# DC27-top.net
KiCad netlist of a schematic drawn in EAGLE
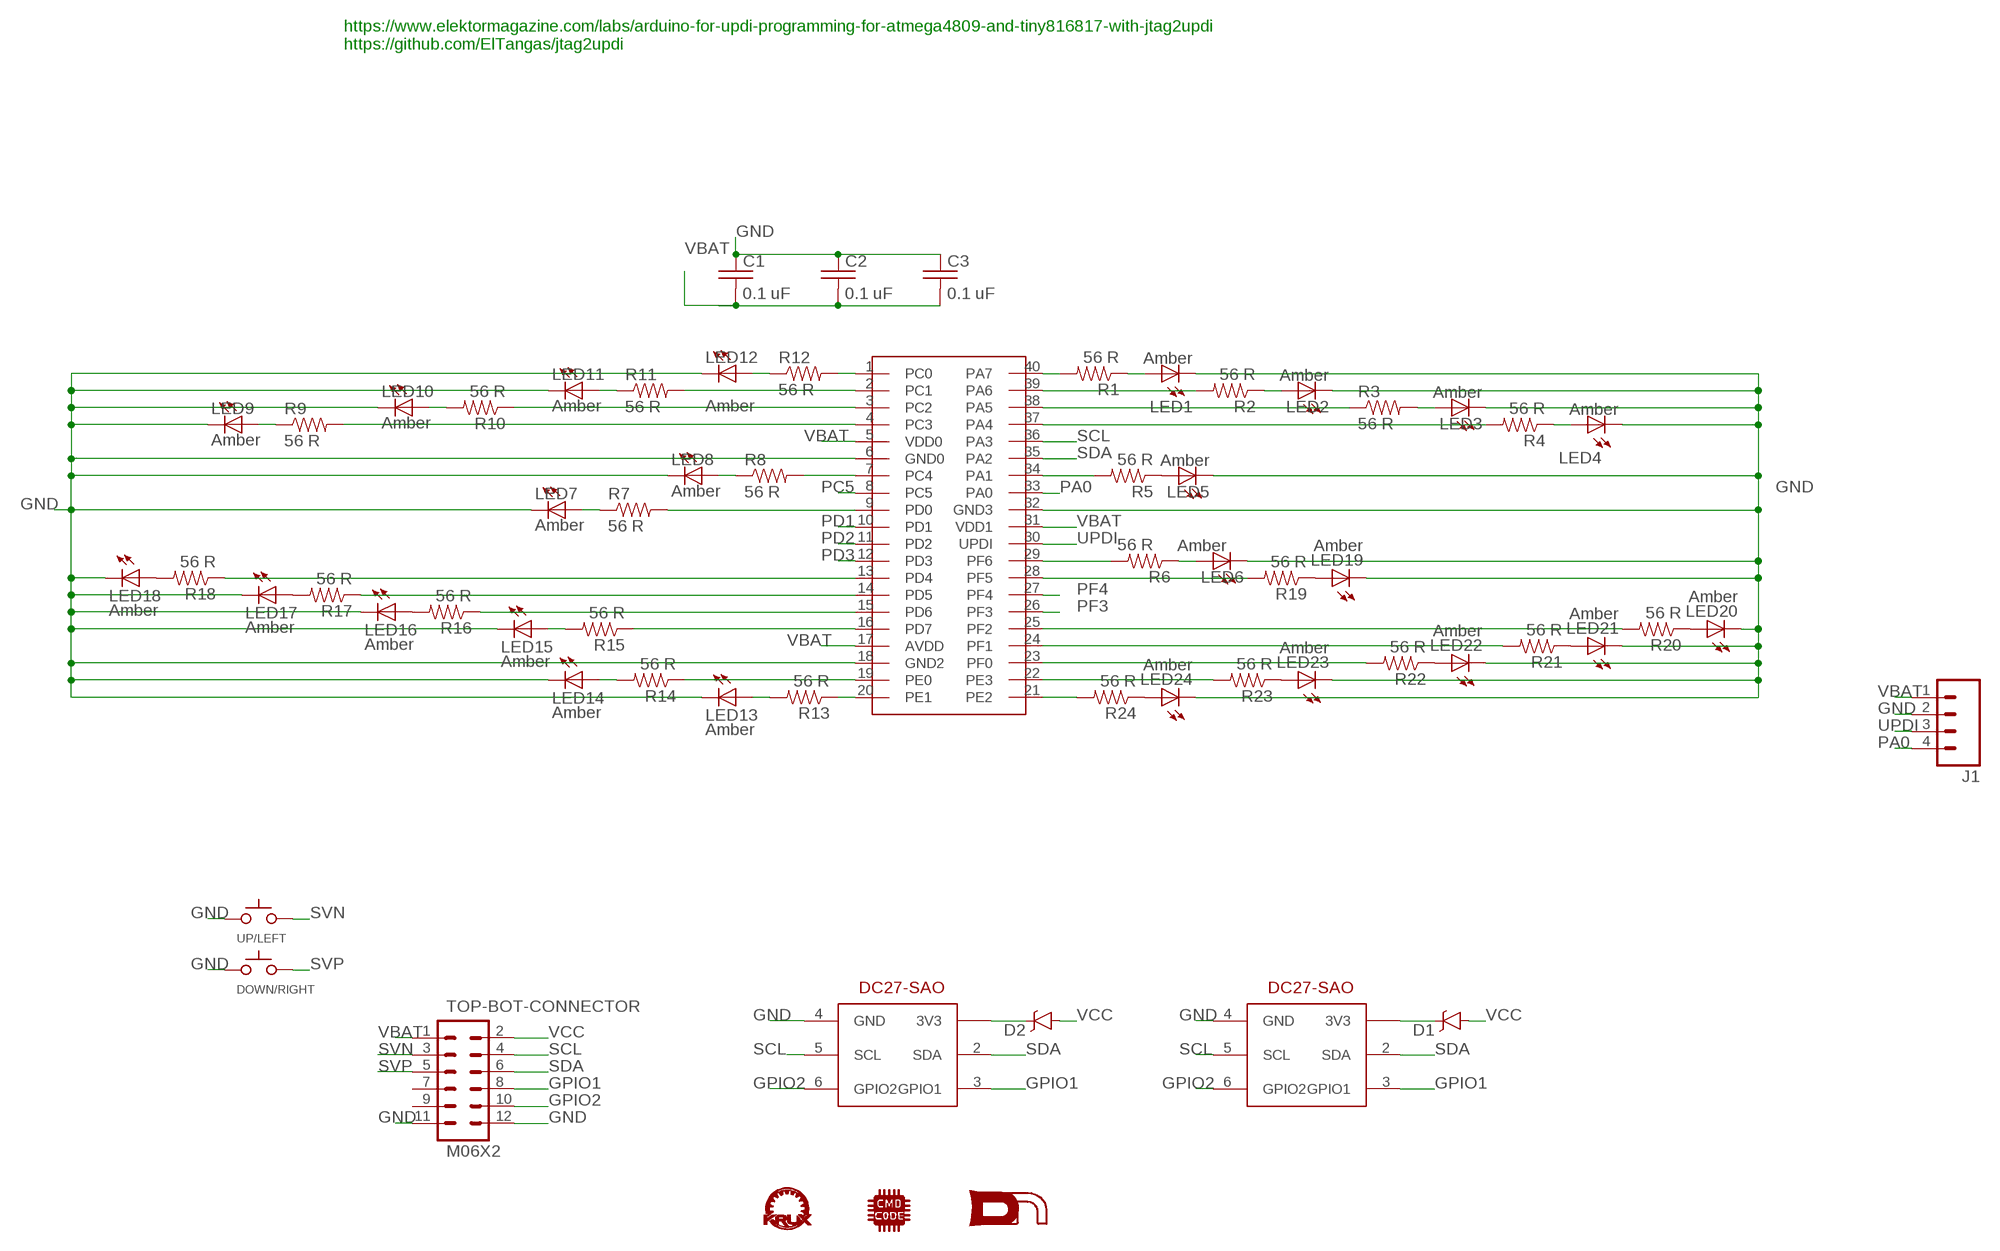
[diagram p0: schematic, sheet 1]

(export (version "E")
  (design (tool "Eeschema 10.0.6"))
  (components
    (comp (ref "C1")
      (value "0.1 uF")
      (footprint "eagle-import:C1206")
      (libsource (lib "eagle-import") (part "C-USC1206"))
    )
    (comp (ref "C2")
      (value "0.1 uF")
      (footprint "eagle-import:C1206")
      (libsource (lib "eagle-import") (part "C-USC1206"))
    )
    (comp (ref "C3")
      (value "0.1 uF")
      (footprint "eagle-import:C1206")
      (libsource (lib "eagle-import") (part "C-USC1206"))
    )
    (comp (ref "D1")
      (value "DIODE-SCHOTTKYDIOAD-TH")
      (footprint "eagle-import:DIOAD1060W80L520D270")
      (libsource (lib "eagle-import") (part "DIODE-SCHOTTKYDIOAD-TH"))
    )
    (comp (ref "D2")
      (value "DIODE-SCHOTTKYDIOAD-TH")
      (footprint "eagle-import:DIOAD1060W80L520D270")
      (libsource (lib "eagle-import") (part "DIODE-SCHOTTKYDIOAD-TH"))
    )
    (comp (ref "DOWN/RIGHT")
      (value "SWITCH_TACTILETACTILE-2PIN-NARROW")
      (footprint "eagle-import:TACTILE-2PIN-NARROW")
      (libsource (lib "eagle-import") (part "SWITCH_TACTILETACTILE-2PIN-NARROW"))
    )
    (comp (ref "J1")
      (value "M04PTH")
      (footprint "eagle-import:1X04")
      (libsource (lib "eagle-import") (part "M04PTH"))
    )
    (comp (ref "LED1")
      (value "Amber")
      (footprint "eagle-import:GULLWING_LED")
      (libsource (lib "eagle-import") (part "LEDREVERSEMOUNT"))
    )
    (comp (ref "LED2")
      (value "Amber")
      (footprint "eagle-import:GULLWING_LED")
      (libsource (lib "eagle-import") (part "LEDREVERSEMOUNT"))
    )
    (comp (ref "LED3")
      (value "Amber")
      (footprint "eagle-import:GULLWING_LED")
      (libsource (lib "eagle-import") (part "LEDREVERSEMOUNT"))
    )
    (comp (ref "LED4")
      (value "Amber")
      (footprint "eagle-import:GULLWING_LED")
      (libsource (lib "eagle-import") (part "LEDREVERSEMOUNT"))
    )
    (comp (ref "LED5")
      (value "Amber")
      (footprint "eagle-import:GULLWING_LED")
      (libsource (lib "eagle-import") (part "LEDREVERSEMOUNT"))
    )
    (comp (ref "LED6")
      (value "Amber")
      (footprint "eagle-import:GULLWING_LED")
      (libsource (lib "eagle-import") (part "LEDREVERSEMOUNT"))
    )
    (comp (ref "LED7")
      (value "Amber")
      (footprint "eagle-import:GULLWING_LED")
      (libsource (lib "eagle-import") (part "LEDREVERSEMOUNT"))
    )
    (comp (ref "LED8")
      (value "Amber")
      (footprint "eagle-import:GULLWING_LED")
      (libsource (lib "eagle-import") (part "LEDREVERSEMOUNT"))
    )
    (comp (ref "LED9")
      (value "Amber")
      (footprint "eagle-import:GULLWING_LED")
      (libsource (lib "eagle-import") (part "LEDREVERSEMOUNT"))
    )
    (comp (ref "LED10")
      (value "Amber")
      (footprint "eagle-import:GULLWING_LED")
      (libsource (lib "eagle-import") (part "LEDREVERSEMOUNT"))
    )
    (comp (ref "LED11")
      (value "Amber")
      (footprint "eagle-import:GULLWING_LED")
      (libsource (lib "eagle-import") (part "LEDREVERSEMOUNT"))
    )
    (comp (ref "LED12")
      (value "Amber")
      (footprint "eagle-import:GULLWING_LED")
      (libsource (lib "eagle-import") (part "LEDREVERSEMOUNT"))
    )
    (comp (ref "LED13")
      (value "Amber")
      (footprint "eagle-import:GULLWING_LED")
      (libsource (lib "eagle-import") (part "LEDREVERSEMOUNT"))
    )
    (comp (ref "LED14")
      (value "Amber")
      (footprint "eagle-import:GULLWING_LED")
      (libsource (lib "eagle-import") (part "LEDREVERSEMOUNT"))
    )
    (comp (ref "LED15")
      (value "Amber")
      (footprint "eagle-import:GULLWING_LED")
      (libsource (lib "eagle-import") (part "LEDREVERSEMOUNT"))
    )
    (comp (ref "LED16")
      (value "Amber")
      (footprint "eagle-import:GULLWING_LED")
      (libsource (lib "eagle-import") (part "LEDREVERSEMOUNT"))
    )
    (comp (ref "LED17")
      (value "Amber")
      (footprint "eagle-import:GULLWING_LED")
      (libsource (lib "eagle-import") (part "LEDREVERSEMOUNT"))
    )
    (comp (ref "LED18")
      (value "Amber")
      (footprint "eagle-import:GULLWING_LED")
      (libsource (lib "eagle-import") (part "LEDREVERSEMOUNT"))
    )
    (comp (ref "LED19")
      (value "Amber")
      (footprint "eagle-import:GULLWING_LED")
      (libsource (lib "eagle-import") (part "LEDREVERSEMOUNT"))
    )
    (comp (ref "LED20")
      (value "Amber")
      (footprint "eagle-import:GULLWING_LED")
      (libsource (lib "eagle-import") (part "LEDREVERSEMOUNT"))
    )
    (comp (ref "LED21")
      (value "Amber")
      (footprint "eagle-import:GULLWING_LED")
      (libsource (lib "eagle-import") (part "LEDREVERSEMOUNT"))
    )
    (comp (ref "LED22")
      (value "Amber")
      (footprint "eagle-import:GULLWING_LED")
      (libsource (lib "eagle-import") (part "LEDREVERSEMOUNT"))
    )
    (comp (ref "LED23")
      (value "Amber")
      (footprint "eagle-import:GULLWING_LED")
      (libsource (lib "eagle-import") (part "LEDREVERSEMOUNT"))
    )
    (comp (ref "LED24")
      (value "Amber")
      (footprint "eagle-import:GULLWING_LED")
      (libsource (lib "eagle-import") (part "LEDREVERSEMOUNT"))
    )
    (comp (ref "R1")
      (value "56 R")
      (footprint "eagle-import:1206")
      (libsource (lib "eagle-import") (part "RESISTOR1206"))
    )
    (comp (ref "R2")
      (value "56 R")
      (footprint "eagle-import:1206")
      (libsource (lib "eagle-import") (part "RESISTOR1206"))
    )
    (comp (ref "R3")
      (value "56 R")
      (footprint "eagle-import:1206")
      (libsource (lib "eagle-import") (part "RESISTOR1206"))
    )
    (comp (ref "R4")
      (value "56 R")
      (footprint "eagle-import:1206")
      (libsource (lib "eagle-import") (part "RESISTOR1206"))
    )
    (comp (ref "R5")
      (value "56 R")
      (footprint "eagle-import:1206")
      (libsource (lib "eagle-import") (part "RESISTOR1206"))
    )
    (comp (ref "R6")
      (value "56 R")
      (footprint "eagle-import:1206")
      (libsource (lib "eagle-import") (part "RESISTOR1206"))
    )
    (comp (ref "R7")
      (value "56 R")
      (footprint "eagle-import:1206")
      (libsource (lib "eagle-import") (part "RESISTOR1206"))
    )
    (comp (ref "R8")
      (value "56 R")
      (footprint "eagle-import:1206")
      (libsource (lib "eagle-import") (part "RESISTOR1206"))
    )
    (comp (ref "R9")
      (value "56 R")
      (footprint "eagle-import:1206")
      (libsource (lib "eagle-import") (part "RESISTOR1206"))
    )
    (comp (ref "R10")
      (value "56 R")
      (footprint "eagle-import:1206")
      (libsource (lib "eagle-import") (part "RESISTOR1206"))
    )
    (comp (ref "R11")
      (value "56 R")
      (footprint "eagle-import:1206")
      (libsource (lib "eagle-import") (part "RESISTOR1206"))
    )
    (comp (ref "R12")
      (value "56 R")
      (footprint "eagle-import:1206")
      (libsource (lib "eagle-import") (part "RESISTOR1206"))
    )
    (comp (ref "R13")
      (value "56 R")
      (footprint "eagle-import:1206")
      (libsource (lib "eagle-import") (part "RESISTOR1206"))
    )
    (comp (ref "R14")
      (value "56 R")
      (footprint "eagle-import:1206")
      (libsource (lib "eagle-import") (part "RESISTOR1206"))
    )
    (comp (ref "R15")
      (value "56 R")
      (footprint "eagle-import:1206")
      (libsource (lib "eagle-import") (part "RESISTOR1206"))
    )
    (comp (ref "R16")
      (value "56 R")
      (footprint "eagle-import:1206")
      (libsource (lib "eagle-import") (part "RESISTOR1206"))
    )
    (comp (ref "R17")
      (value "56 R")
      (footprint "eagle-import:1206")
      (libsource (lib "eagle-import") (part "RESISTOR1206"))
    )
    (comp (ref "R18")
      (value "56 R")
      (footprint "eagle-import:1206")
      (libsource (lib "eagle-import") (part "RESISTOR1206"))
    )
    (comp (ref "R19")
      (value "56 R")
      (footprint "eagle-import:1206")
      (libsource (lib "eagle-import") (part "RESISTOR1206"))
    )
    (comp (ref "R20")
      (value "56 R")
      (footprint "eagle-import:1206")
      (libsource (lib "eagle-import") (part "RESISTOR1206"))
    )
    (comp (ref "R21")
      (value "56 R")
      (footprint "eagle-import:1206")
      (libsource (lib "eagle-import") (part "RESISTOR1206"))
    )
    (comp (ref "R22")
      (value "56 R")
      (footprint "eagle-import:1206")
      (libsource (lib "eagle-import") (part "RESISTOR1206"))
    )
    (comp (ref "R23")
      (value "56 R")
      (footprint "eagle-import:1206")
      (libsource (lib "eagle-import") (part "RESISTOR1206"))
    )
    (comp (ref "R24")
      (value "56 R")
      (footprint "eagle-import:1206")
      (libsource (lib "eagle-import") (part "RESISTOR1206"))
    )
    (comp (ref "TOP-BOT-CONNECTOR")
      (value "M06X2")
      (footprint "eagle-import:2X6")
      (libsource (lib "eagle-import") (part "M06X2"))
    )
    (comp (ref "U$1")
      (value "KRUX_LOGO")
      (footprint "eagle-import:KRUX_LOGO")
      (libsource (lib "eagle-import") (part "KRUX_LOGO"))
    )
    (comp (ref "U$2")
      (value "CMD_C0DE_LOGO")
      (footprint "eagle-import:CMD_C0DE_LOGO")
      (libsource (lib "eagle-import") (part "CMD_C0DE_LOGO"))
    )
    (comp (ref "U$3")
      (value "DC-27-SAO")
      (footprint "eagle-import:3X2")
      (libsource (lib "eagle-import") (part "DC-27-SAO"))
    )
    (comp (ref "U$4")
      (value "DC-27-SAO")
      (footprint "eagle-import:3X2")
      (libsource (lib "eagle-import") (part "DC-27-SAO"))
    )
    (comp (ref "U$5")
      (value "DN_LOGODC26")
      (footprint "eagle-import:DN_LOGO_DC26")
      (libsource (lib "eagle-import") (part "DN_LOGODC26"))
    )
    (comp (ref "U$6")
      (value "ATMEGA4809-PFATMEL4809-PF")
      (footprint "eagle-import:DIP1587W58P254L5175H635Q40B")
      (libsource (lib "eagle-import") (part "ATMEGA4809-PFATMEL4809-PF"))
    )
    (comp (ref "UP/LEFT")
      (value "SWITCH_TACTILETACTILE-2PIN-NARROW")
      (footprint "eagle-import:TACTILE-2PIN-NARROW")
      (libsource (lib "eagle-import") (part "SWITCH_TACTILETACTILE-2PIN-NARROW"))
    )
  )
  (nets
    (net (code "1") (name "/GND") (class "Default")
      (node (ref "C1") (pin "1") (pinfunction "1_1") (pintype "passive"))
      (node (ref "C2") (pin "1") (pinfunction "1_1") (pintype "passive"))
      (node (ref "C3") (pin "1") (pinfunction "1_1") (pintype "passive"))
      (node (ref "DOWN/RIGHT") (pin "P$2") (pinfunction "C_P$2") (pintype "passive"))
      (node (ref "J1") (pin "2") (pinfunction "2_2") (pintype "passive"))
      (node (ref "LED1") (pin "C") (pinfunction "C_C") (pintype "output"))
      (node (ref "LED10") (pin "C") (pinfunction "C_C") (pintype "output"))
      (node (ref "LED11") (pin "C") (pinfunction "C_C") (pintype "output"))
      (node (ref "LED12") (pin "C") (pinfunction "C_C") (pintype "output"))
      (node (ref "LED13") (pin "C") (pinfunction "C_C") (pintype "output"))
      (node (ref "LED14") (pin "C") (pinfunction "C_C") (pintype "output"))
      (node (ref "LED15") (pin "C") (pinfunction "C_C") (pintype "output"))
      (node (ref "LED16") (pin "C") (pinfunction "C_C") (pintype "output"))
      (node (ref "LED17") (pin "C") (pinfunction "C_C") (pintype "output"))
      (node (ref "LED18") (pin "C") (pinfunction "C_C") (pintype "output"))
      (node (ref "LED19") (pin "C") (pinfunction "C_C") (pintype "output"))
      (node (ref "LED2") (pin "C") (pinfunction "C_C") (pintype "output"))
      (node (ref "LED20") (pin "C") (pinfunction "C_C") (pintype "output"))
      (node (ref "LED21") (pin "C") (pinfunction "C_C") (pintype "output"))
      (node (ref "LED22") (pin "C") (pinfunction "C_C") (pintype "output"))
      (node (ref "LED23") (pin "C") (pinfunction "C_C") (pintype "output"))
      (node (ref "LED24") (pin "C") (pinfunction "C_C") (pintype "output"))
      (node (ref "LED3") (pin "C") (pinfunction "C_C") (pintype "output"))
      (node (ref "LED4") (pin "C") (pinfunction "C_C") (pintype "output"))
      (node (ref "LED5") (pin "C") (pinfunction "C_C") (pintype "output"))
      (node (ref "LED6") (pin "C") (pinfunction "C_C") (pintype "output"))
      (node (ref "LED7") (pin "C") (pinfunction "C_C") (pintype "output"))
      (node (ref "LED8") (pin "C") (pinfunction "C_C") (pintype "output"))
      (node (ref "LED9") (pin "C") (pinfunction "C_C") (pintype "output"))
      (node (ref "TOP-BOT-CONNECTOR") (pin "11") (pinfunction "11_11") (pintype "passive"))
      (node (ref "TOP-BOT-CONNECTOR") (pin "12") (pinfunction "12_12") (pintype "passive"))
      (node (ref "U$3") (pin "4") (pinfunction "GND_4") (pintype "power_in"))
      (node (ref "U$4") (pin "4") (pinfunction "GND_4") (pintype "power_in"))
      (node (ref "U$6") (pin "18") (pinfunction "GND2_18") (pintype "bidirectional"))
      (node (ref "U$6") (pin "32") (pinfunction "GND3_32") (pintype "bidirectional"))
      (node (ref "U$6") (pin "6") (pinfunction "GND0_6") (pintype "bidirectional"))
      (node (ref "UP/LEFT") (pin "P$2") (pinfunction "C_P$2") (pintype "passive"))
    )
    (net (code "2") (name "/GPIO1") (class "Default")
      (node (ref "TOP-BOT-CONNECTOR") (pin "8") (pinfunction "8_8") (pintype "passive"))
      (node (ref "U$3") (pin "3") (pinfunction "GPIO1_3") (pintype "bidirectional"))
      (node (ref "U$4") (pin "3") (pinfunction "GPIO1_3") (pintype "bidirectional"))
    )
    (net (code "3") (name "/GPIO2") (class "Default")
      (node (ref "TOP-BOT-CONNECTOR") (pin "10") (pinfunction "10_10") (pintype "passive"))
      (node (ref "U$3") (pin "6") (pinfunction "GPIO2_6") (pintype "bidirectional"))
      (node (ref "U$4") (pin "6") (pinfunction "GPIO2_6") (pintype "bidirectional"))
    )
    (net (code "4") (name "/PA0") (class "Default")
      (node (ref "J1") (pin "4") (pinfunction "4_4") (pintype "passive"))
      (node (ref "U$6") (pin "33") (pinfunction "PA0_33") (pintype "bidirectional"))
    )
    (net (code "5") (name "/PC5") (class "Default")
      (node (ref "U$6") (pin "8") (pinfunction "PC5_8") (pintype "bidirectional"))
    )
    (net (code "6") (name "/PD1") (class "Default")
      (node (ref "U$6") (pin "10") (pinfunction "PD1_10") (pintype "bidirectional"))
    )
    (net (code "7") (name "/PD2") (class "Default")
      (node (ref "U$6") (pin "11") (pinfunction "PD2_11") (pintype "bidirectional"))
    )
    (net (code "8") (name "/PD3") (class "Default")
      (node (ref "U$6") (pin "12") (pinfunction "PD3_12") (pintype "bidirectional"))
    )
    (net (code "9") (name "/PF3") (class "Default")
      (node (ref "U$6") (pin "26") (pinfunction "PF3_26") (pintype "bidirectional"))
    )
    (net (code "10") (name "/PF4") (class "Default")
      (node (ref "U$6") (pin "27") (pinfunction "PF4_27") (pintype "bidirectional"))
    )
    (net (code "11") (name "/SCL") (class "Default")
      (node (ref "TOP-BOT-CONNECTOR") (pin "4") (pinfunction "4_4") (pintype "passive"))
      (node (ref "U$3") (pin "5") (pinfunction "SCL_5") (pintype "bidirectional"))
      (node (ref "U$4") (pin "5") (pinfunction "SCL_5") (pintype "bidirectional"))
      (node (ref "U$6") (pin "36") (pinfunction "PA3_36") (pintype "bidirectional"))
    )
    (net (code "12") (name "/SDA") (class "Default")
      (node (ref "TOP-BOT-CONNECTOR") (pin "6") (pinfunction "6_6") (pintype "passive"))
      (node (ref "U$3") (pin "2") (pinfunction "SDA_2") (pintype "bidirectional"))
      (node (ref "U$4") (pin "2") (pinfunction "SDA_2") (pintype "bidirectional"))
      (node (ref "U$6") (pin "35") (pinfunction "PA2_35") (pintype "bidirectional"))
    )
    (net (code "13") (name "/SVN") (class "Default")
      (node (ref "TOP-BOT-CONNECTOR") (pin "3") (pinfunction "3_3") (pintype "passive"))
      (node (ref "UP/LEFT") (pin "P$1") (pinfunction "A_P$1") (pintype "passive"))
    )
    (net (code "14") (name "/SVP") (class "Default")
      (node (ref "DOWN/RIGHT") (pin "P$1") (pinfunction "A_P$1") (pintype "passive"))
      (node (ref "TOP-BOT-CONNECTOR") (pin "5") (pinfunction "5_5") (pintype "passive"))
    )
    (net (code "15") (name "/UPDI") (class "Default")
      (node (ref "J1") (pin "3") (pinfunction "3_3") (pintype "passive"))
      (node (ref "U$6") (pin "30") (pinfunction "UPDI_30") (pintype "bidirectional"))
    )
    (net (code "16") (name "/VBAT") (class "Default")
      (node (ref "C1") (pin "2") (pinfunction "2_2") (pintype "passive"))
      (node (ref "C2") (pin "2") (pinfunction "2_2") (pintype "passive"))
      (node (ref "C3") (pin "2") (pinfunction "2_2") (pintype "passive"))
      (node (ref "J1") (pin "1") (pinfunction "1_1") (pintype "passive"))
      (node (ref "TOP-BOT-CONNECTOR") (pin "1") (pinfunction "1_1") (pintype "passive"))
      (node (ref "U$6") (pin "17") (pinfunction "AVDD_17") (pintype "power_in"))
      (node (ref "U$6") (pin "31") (pinfunction "VDD1_31") (pintype "power_in"))
      (node (ref "U$6") (pin "5") (pinfunction "VDD0_5") (pintype "power_in"))
    )
    (net (code "17") (name "/VCC") (class "Default")
      (node (ref "D1") (pin "A") (pinfunction "A_A") (pintype "passive"))
      (node (ref "D2") (pin "A") (pinfunction "A_A") (pintype "passive"))
      (node (ref "TOP-BOT-CONNECTOR") (pin "2") (pinfunction "2_2") (pintype "passive"))
    )
    (net (code "18") (name "Net-(LED1-PadA)") (class "Default")
      (node (ref "LED1") (pin "A") (pinfunction "A_A") (pintype "input"))
      (node (ref "R1") (pin "1") (pinfunction "1_1") (pintype "passive"))
    )
    (net (code "19") (name "Net-(LED2-PadA)") (class "Default")
      (node (ref "LED2") (pin "A") (pinfunction "A_A") (pintype "input"))
      (node (ref "R2") (pin "1") (pinfunction "1_1") (pintype "passive"))
    )
    (net (code "20") (name "Net-(LED3-PadA)") (class "Default")
      (node (ref "LED3") (pin "A") (pinfunction "A_A") (pintype "input"))
      (node (ref "R3") (pin "2") (pinfunction "2_2") (pintype "passive"))
    )
    (net (code "21") (name "Net-(LED4-PadA)") (class "Default")
      (node (ref "LED4") (pin "A") (pinfunction "A_A") (pintype "input"))
      (node (ref "R4") (pin "1") (pinfunction "1_1") (pintype "passive"))
    )
    (net (code "22") (name "Net-(LED5-PadA)") (class "Default")
      (node (ref "LED5") (pin "A") (pinfunction "A_A") (pintype "input"))
      (node (ref "R5") (pin "1") (pinfunction "1_1") (pintype "passive"))
    )
    (net (code "23") (name "Net-(LED6-PadA)") (class "Default")
      (node (ref "LED6") (pin "A") (pinfunction "A_A") (pintype "input"))
      (node (ref "R6") (pin "1") (pinfunction "1_1") (pintype "passive"))
    )
    (net (code "24") (name "Net-(LED7-PadA)") (class "Default")
      (node (ref "LED7") (pin "A") (pinfunction "A_A") (pintype "input"))
      (node (ref "R7") (pin "1") (pinfunction "1_1") (pintype "passive"))
    )
    (net (code "25") (name "Net-(LED8-PadA)") (class "Default")
      (node (ref "LED8") (pin "A") (pinfunction "A_A") (pintype "input"))
      (node (ref "R8") (pin "1") (pinfunction "1_1") (pintype "passive"))
    )
    (net (code "26") (name "Net-(LED9-PadA)") (class "Default")
      (node (ref "LED9") (pin "A") (pinfunction "A_A") (pintype "input"))
      (node (ref "R9") (pin "1") (pinfunction "1_1") (pintype "passive"))
    )
    (net (code "27") (name "Net-(LED10-PadA)") (class "Default")
      (node (ref "LED10") (pin "A") (pinfunction "A_A") (pintype "input"))
      (node (ref "R10") (pin "2") (pinfunction "2_2") (pintype "passive"))
    )
    (net (code "28") (name "Net-(LED11-PadA)") (class "Default")
      (node (ref "LED11") (pin "A") (pinfunction "A_A") (pintype "input"))
      (node (ref "R11") (pin "1") (pinfunction "1_1") (pintype "passive"))
    )
    (net (code "29") (name "Net-(LED12-PadA)") (class "Default")
      (node (ref "LED12") (pin "A") (pinfunction "A_A") (pintype "input"))
      (node (ref "R12") (pin "1") (pinfunction "1_1") (pintype "passive"))
    )
    (net (code "30") (name "Net-(LED13-PadA)") (class "Default")
      (node (ref "LED13") (pin "A") (pinfunction "A_A") (pintype "input"))
      (node (ref "R13") (pin "2") (pinfunction "2_2") (pintype "passive"))
    )
    (net (code "31") (name "Net-(LED14-PadA)") (class "Default")
      (node (ref "LED14") (pin "A") (pinfunction "A_A") (pintype "input"))
      (node (ref "R14") (pin "2") (pinfunction "2_2") (pintype "passive"))
    )
    (net (code "32") (name "Net-(LED15-PadA)") (class "Default")
      (node (ref "LED15") (pin "A") (pinfunction "A_A") (pintype "input"))
      (node (ref "R15") (pin "2") (pinfunction "2_2") (pintype "passive"))
    )
    (net (code "33") (name "Net-(LED16-PadA)") (class "Default")
      (node (ref "LED16") (pin "A") (pinfunction "A_A") (pintype "input"))
      (node (ref "R16") (pin "2") (pinfunction "2_2") (pintype "passive"))
    )
    (net (code "34") (name "Net-(LED17-PadA)") (class "Default")
      (node (ref "LED17") (pin "A") (pinfunction "A_A") (pintype "input"))
      (node (ref "R17") (pin "2") (pinfunction "2_2") (pintype "passive"))
    )
    (net (code "35") (name "Net-(LED18-PadA)") (class "Default")
      (node (ref "LED18") (pin "A") (pinfunction "A_A") (pintype "input"))
      (node (ref "R18") (pin "2") (pinfunction "2_2") (pintype "passive"))
    )
    (net (code "36") (name "Net-(LED19-PadA)") (class "Default")
      (node (ref "LED19") (pin "A") (pinfunction "A_A") (pintype "input"))
      (node (ref "R19") (pin "1") (pinfunction "1_1") (pintype "passive"))
    )
    (net (code "37") (name "Net-(LED20-PadA)") (class "Default")
      (node (ref "LED20") (pin "A") (pinfunction "A_A") (pintype "input"))
      (node (ref "R20") (pin "1") (pinfunction "1_1") (pintype "passive"))
    )
    (net (code "38") (name "Net-(LED21-PadA)") (class "Default")
      (node (ref "LED21") (pin "A") (pinfunction "A_A") (pintype "input"))
      (node (ref "R21") (pin "1") (pinfunction "1_1") (pintype "passive"))
    )
    (net (code "39") (name "Net-(LED22-PadA)") (class "Default")
      (node (ref "LED22") (pin "A") (pinfunction "A_A") (pintype "input"))
      (node (ref "R22") (pin "1") (pinfunction "1_1") (pintype "passive"))
    )
    (net (code "40") (name "Net-(LED23-PadA)") (class "Default")
      (node (ref "LED23") (pin "A") (pinfunction "A_A") (pintype "input"))
      (node (ref "R23") (pin "1") (pinfunction "1_1") (pintype "passive"))
    )
    (net (code "41") (name "Net-(LED24-PadA)") (class "Default")
      (node (ref "LED24") (pin "A") (pinfunction "A_A") (pintype "input"))
      (node (ref "R24") (pin "1") (pinfunction "1_1") (pintype "passive"))
    )
    (net (code "42") (name "Net-(U$3-3V3)") (class "Default")
      (node (ref "D2") (pin "C") (pinfunction "C_C") (pintype "passive"))
      (node (ref "U$3") (pin "1") (pinfunction "3V3_1") (pintype "power_in"))
    )
    (net (code "43") (name "Net-(U$4-3V3)") (class "Default")
      (node (ref "D1") (pin "C") (pinfunction "C_C") (pintype "passive"))
      (node (ref "U$4") (pin "1") (pinfunction "3V3_1") (pintype "power_in"))
    )
    (net (code "44") (name "Net-(U$6-PA1)") (class "Default")
      (node (ref "R5") (pin "2") (pinfunction "2_2") (pintype "passive"))
      (node (ref "U$6") (pin "34") (pinfunction "PA1_34") (pintype "bidirectional"))
    )
    (net (code "45") (name "Net-(U$6-PA4)") (class "Default")
      (node (ref "R4") (pin "2") (pinfunction "2_2") (pintype "passive"))
      (node (ref "U$6") (pin "37") (pinfunction "PA4_37") (pintype "bidirectional"))
    )
    (net (code "46") (name "Net-(U$6-PA5)") (class "Default")
      (node (ref "R3") (pin "1") (pinfunction "1_1") (pintype "passive"))
      (node (ref "U$6") (pin "38") (pinfunction "PA5_38") (pintype "bidirectional"))
    )
    (net (code "47") (name "Net-(U$6-PA6)") (class "Default")
      (node (ref "R2") (pin "2") (pinfunction "2_2") (pintype "passive"))
      (node (ref "U$6") (pin "39") (pinfunction "PA6_39") (pintype "bidirectional"))
    )
    (net (code "48") (name "Net-(U$6-PA7)") (class "Default")
      (node (ref "R1") (pin "2") (pinfunction "2_2") (pintype "passive"))
      (node (ref "U$6") (pin "40") (pinfunction "PA7_40") (pintype "bidirectional"))
    )
    (net (code "49") (name "Net-(U$6-PC0)") (class "Default")
      (node (ref "R12") (pin "2") (pinfunction "2_2") (pintype "passive"))
      (node (ref "U$6") (pin "1") (pinfunction "PC0_1") (pintype "bidirectional"))
    )
    (net (code "50") (name "Net-(U$6-PC1)") (class "Default")
      (node (ref "R11") (pin "2") (pinfunction "2_2") (pintype "passive"))
      (node (ref "U$6") (pin "2") (pinfunction "PC1_2") (pintype "bidirectional"))
    )
    (net (code "51") (name "Net-(U$6-PC2)") (class "Default")
      (node (ref "R10") (pin "1") (pinfunction "1_1") (pintype "passive"))
      (node (ref "U$6") (pin "3") (pinfunction "PC2_3") (pintype "bidirectional"))
    )
    (net (code "52") (name "Net-(U$6-PC3)") (class "Default")
      (node (ref "R9") (pin "2") (pinfunction "2_2") (pintype "passive"))
      (node (ref "U$6") (pin "4") (pinfunction "PC3_4") (pintype "bidirectional"))
    )
    (net (code "53") (name "Net-(U$6-PC4)") (class "Default")
      (node (ref "R8") (pin "2") (pinfunction "2_2") (pintype "passive"))
      (node (ref "U$6") (pin "7") (pinfunction "PC4_7") (pintype "bidirectional"))
    )
    (net (code "54") (name "Net-(U$6-PD0)") (class "Default")
      (node (ref "R7") (pin "2") (pinfunction "2_2") (pintype "passive"))
      (node (ref "U$6") (pin "9") (pinfunction "PD0_9") (pintype "bidirectional"))
    )
    (net (code "55") (name "Net-(U$6-PD4)") (class "Default")
      (node (ref "R18") (pin "1") (pinfunction "1_1") (pintype "passive"))
      (node (ref "U$6") (pin "13") (pinfunction "PD4_13") (pintype "bidirectional"))
    )
    (net (code "56") (name "Net-(U$6-PD5)") (class "Default")
      (node (ref "R17") (pin "1") (pinfunction "1_1") (pintype "passive"))
      (node (ref "U$6") (pin "14") (pinfunction "PD5_14") (pintype "bidirectional"))
    )
    (net (code "57") (name "Net-(U$6-PD6)") (class "Default")
      (node (ref "R16") (pin "1") (pinfunction "1_1") (pintype "passive"))
      (node (ref "U$6") (pin "15") (pinfunction "PD6_15") (pintype "bidirectional"))
    )
    (net (code "58") (name "Net-(U$6-PD7)") (class "Default")
      (node (ref "R15") (pin "1") (pinfunction "1_1") (pintype "passive"))
      (node (ref "U$6") (pin "16") (pinfunction "PD7_16") (pintype "bidirectional"))
    )
    (net (code "59") (name "Net-(U$6-PE0)") (class "Default")
      (node (ref "R14") (pin "1") (pinfunction "1_1") (pintype "passive"))
      (node (ref "U$6") (pin "19") (pinfunction "PE0_19") (pintype "bidirectional"))
    )
    (net (code "60") (name "Net-(U$6-PE1)") (class "Default")
      (node (ref "R13") (pin "1") (pinfunction "1_1") (pintype "passive"))
      (node (ref "U$6") (pin "20") (pinfunction "PE1_20") (pintype "bidirectional"))
    )
    (net (code "61") (name "Net-(U$6-PE2)") (class "Default")
      (node (ref "R24") (pin "2") (pinfunction "2_2") (pintype "passive"))
      (node (ref "U$6") (pin "21") (pinfunction "PE2_21") (pintype "bidirectional"))
    )
    (net (code "62") (name "Net-(U$6-PE3)") (class "Default")
      (node (ref "R23") (pin "2") (pinfunction "2_2") (pintype "passive"))
      (node (ref "U$6") (pin "22") (pinfunction "PE3_22") (pintype "bidirectional"))
    )
    (net (code "63") (name "Net-(U$6-PF0)") (class "Default")
      (node (ref "R22") (pin "2") (pinfunction "2_2") (pintype "passive"))
      (node (ref "U$6") (pin "23") (pinfunction "PF0_23") (pintype "bidirectional"))
    )
    (net (code "64") (name "Net-(U$6-PF1)") (class "Default")
      (node (ref "R21") (pin "2") (pinfunction "2_2") (pintype "passive"))
      (node (ref "U$6") (pin "24") (pinfunction "PF1_24") (pintype "bidirectional"))
    )
    (net (code "65") (name "Net-(U$6-PF2)") (class "Default")
      (node (ref "R20") (pin "2") (pinfunction "2_2") (pintype "passive"))
      (node (ref "U$6") (pin "25") (pinfunction "PF2_25") (pintype "bidirectional"))
    )
    (net (code "66") (name "Net-(U$6-PF5)") (class "Default")
      (node (ref "R19") (pin "2") (pinfunction "2_2") (pintype "passive"))
      (node (ref "U$6") (pin "28") (pinfunction "PF5_28") (pintype "bidirectional"))
    )
    (net (code "67") (name "Net-(U$6-PF6)") (class "Default")
      (node (ref "R6") (pin "2") (pinfunction "2_2") (pintype "passive"))
      (node (ref "U$6") (pin "29") (pinfunction "PF6_29") (pintype "bidirectional"))
    )
    (net (code "68") (name "unconnected-(TOP-BOT-CONNECTOR-Pad7)") (class "Default")
      (node (ref "TOP-BOT-CONNECTOR") (pin "7") (pinfunction "7_7") (pintype "passive"))
    )
    (net (code "69") (name "unconnected-(TOP-BOT-CONNECTOR-Pad9)") (class "Default")
      (node (ref "TOP-BOT-CONNECTOR") (pin "9") (pinfunction "9_9") (pintype "passive"))
    )
  )
)
